# project_konovalov_motor_driver.net
KiCad netlist of a schematic drawn in Altium Designer
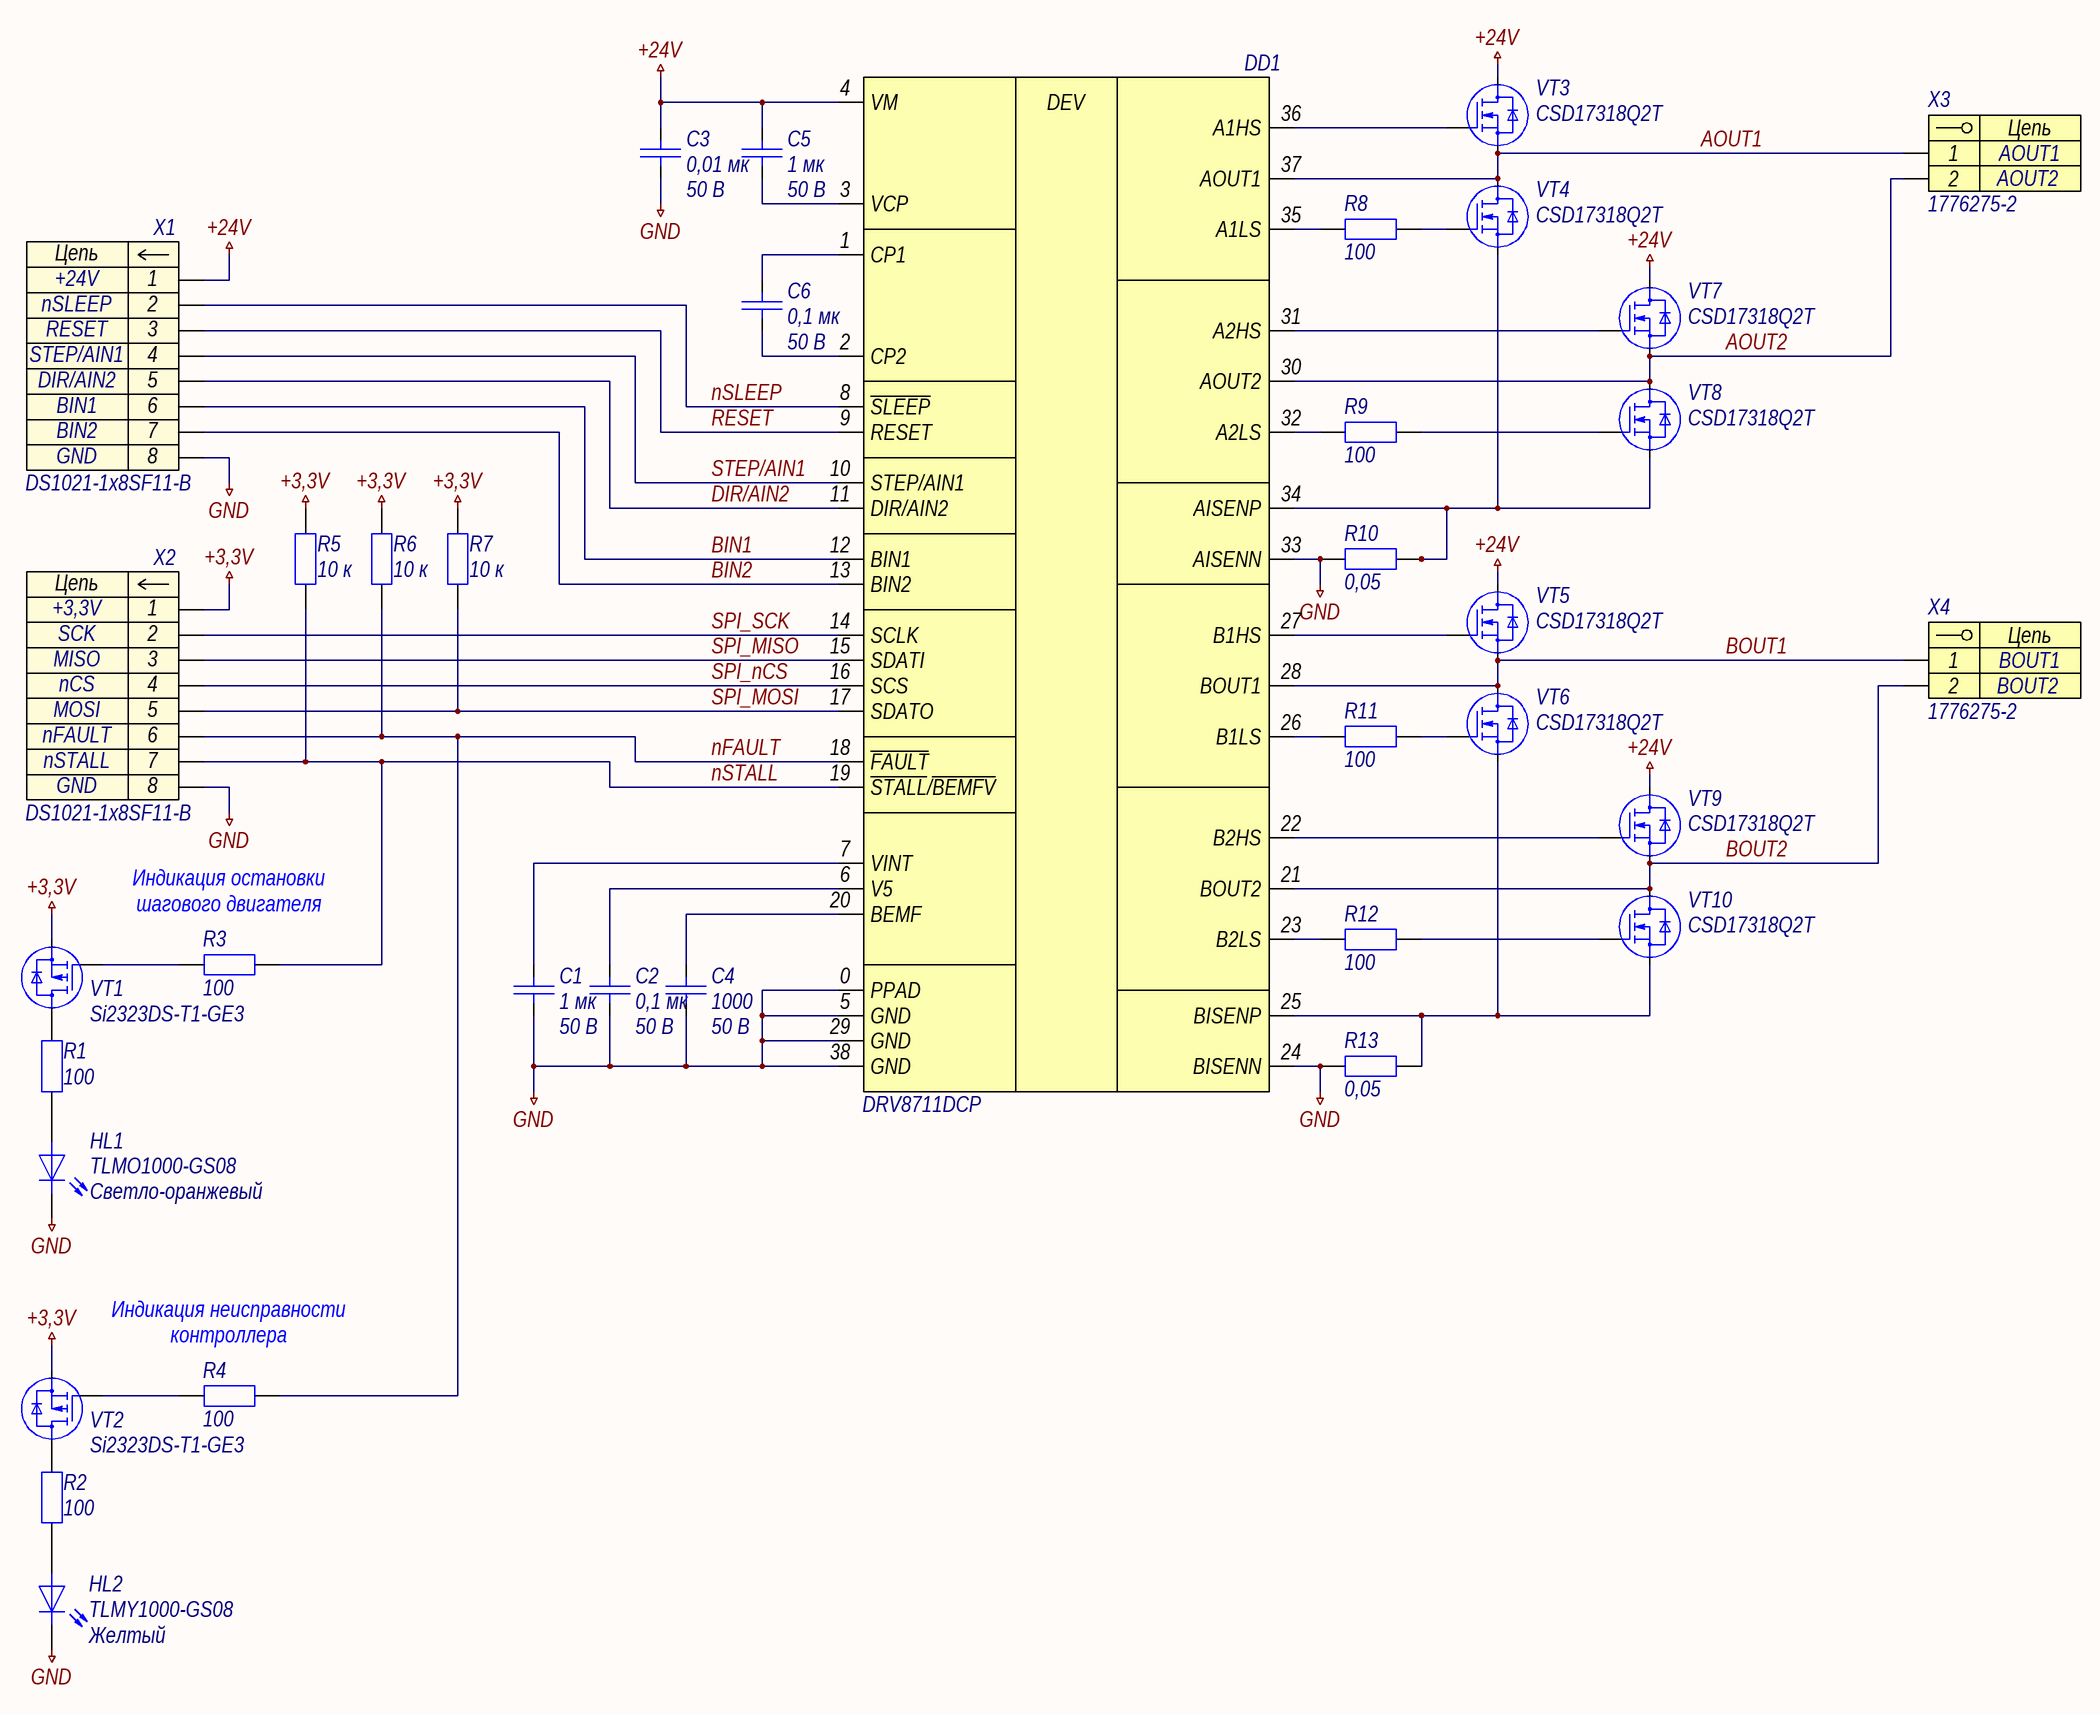
[diagram p0: project_konovalov_motor_driver.SchDoc]

(export (version "E")
  (design (tool "Eeschema 10.0.6"))
  (components
    (comp (ref "C1")
      (value "1 мк")
      (footprint "C0603")
      (description "=Описание")
      (fields (field (name "НАПРЯЖЕНИЕ") "50 В"))
      (libsource (lib "Database_Students") (part "CAPACITOR-NONPOLAR"))
    )
    (comp (ref "C2")
      (value "0,1 мк")
      (footprint "C0603")
      (description "=Описание")
      (fields (field (name "НАПРЯЖЕНИЕ") "50 В"))
      (libsource (lib "Database_Students") (part "CAPACITOR-NONPOLAR"))
    )
    (comp (ref "C3")
      (value "0,01 мк")
      (footprint "C0603")
      (description "=Описание")
      (fields (field (name "НАПРЯЖЕНИЕ") "50 В"))
      (libsource (lib "Database_Students") (part "CAPACITOR-NONPOLAR"))
    )
    (comp (ref "C4")
      (value "1000")
      (footprint "C0603")
      (description "=Описание")
      (fields (field (name "НАПРЯЖЕНИЕ") "50 В"))
      (libsource (lib "Database_Students") (part "CAPACITOR-NONPOLAR"))
    )
    (comp (ref "C5")
      (value "1 мк")
      (footprint "C0603")
      (description "=Описание")
      (fields (field (name "НАПРЯЖЕНИЕ") "50 В"))
      (libsource (lib "Database_Students") (part "CAPACITOR-NONPOLAR"))
    )
    (comp (ref "C6")
      (value "0,1 мк")
      (footprint "C0603")
      (description "=Описание")
      (fields (field (name "НАПРЯЖЕНИЕ") "50 В"))
      (libsource (lib "Database_Students") (part "CAPACITOR-NONPOLAR"))
    )
    (comp (ref "DD1")
      (value "DRV8711DCP")
      (footprint "HTSSOP-38-P50-470X290X120-L63X22-T470X290")
      (description "=Описание")
      (libsource (lib "Database_Students") (part "DRV8711DCP"))
    )
    (comp (ref "HL1")
      (value "TLMO1000-GS08")
      (footprint "HL0603")
      (description "=Описание")
      (fields (field (name "ЦВЕТ") "Светло-оранжевый"))
      (libsource (lib "Database_Students") (part "LED-COMMON"))
    )
    (comp (ref "HL2")
      (value "TLMY1000-GS08")
      (footprint "HL0603")
      (description "=Описание")
      (fields (field (name "ЦВЕТ") "Желтый"))
      (libsource (lib "Database_Students") (part "LED-COMMON"))
    )
    (comp (ref "R1")
      (value "100")
      (footprint "R0603")
      (description "=Описание")
      (libsource (lib "Database_Students") (part "RESISTOR-COMMON"))
    )
    (comp (ref "R2")
      (value "100")
      (footprint "R0603")
      (description "=Описание")
      (libsource (lib "Database_Students") (part "RESISTOR-COMMON"))
    )
    (comp (ref "R3")
      (value "100")
      (footprint "R0603")
      (description "=Описание")
      (libsource (lib "Database_Students") (part "RESISTOR-COMMON"))
    )
    (comp (ref "R4")
      (value "100")
      (footprint "R0603")
      (description "=Описание")
      (libsource (lib "Database_Students") (part "RESISTOR-COMMON"))
    )
    (comp (ref "R5")
      (value "10 к")
      (footprint "R0603")
      (description "=Описание")
      (libsource (lib "Database_Students") (part "RESISTOR-COMMON"))
    )
    (comp (ref "R6")
      (value "10 к")
      (footprint "R0603")
      (description "=Описание")
      (libsource (lib "Database_Students") (part "RESISTOR-COMMON"))
    )
    (comp (ref "R7")
      (value "10 к")
      (footprint "R0603")
      (description "=Описание")
      (libsource (lib "Database_Students") (part "RESISTOR-COMMON"))
    )
    (comp (ref "R8")
      (value "100")
      (footprint "R0603")
      (description "=Описание")
      (libsource (lib "Database_Students") (part "RESISTOR-COMMON"))
    )
    (comp (ref "R9")
      (value "100")
      (footprint "R0603")
      (description "=Описание")
      (libsource (lib "Database_Students") (part "RESISTOR-COMMON"))
    )
    (comp (ref "R10")
      (value "0,05")
      (footprint "R0603")
      (description "=Описание")
      (libsource (lib "Database_Students") (part "RESISTOR-COMMON"))
    )
    (comp (ref "R11")
      (value "100")
      (footprint "R0603")
      (description "=Описание")
      (libsource (lib "Database_Students") (part "RESISTOR-COMMON"))
    )
    (comp (ref "R12")
      (value "100")
      (footprint "R0603")
      (description "=Описание")
      (libsource (lib "Database_Students") (part "RESISTOR-COMMON"))
    )
    (comp (ref "R13")
      (value "0,05")
      (footprint "R0603")
      (description "=Описание")
      (libsource (lib "Database_Students") (part "RESISTOR-COMMON"))
    )
    (comp (ref "VT1")
      (value "Si2323DS-T1-GE3")
      (footprint "SOT-23-3-P95-292X237X112")
      (description "=Описание")
      (libsource (lib "Database_Students") (part "MOSFET-P-DIODE"))
    )
    (comp (ref "VT2")
      (value "Si2323DS-T1-GE3")
      (footprint "SOT-23-3-P95-292X237X112")
      (description "=Описание")
      (libsource (lib "Database_Students") (part "MOSFET-P-DIODE"))
    )
    (comp (ref "VT3")
      (value "CSD17318Q2T")
      (footprint "WSON-6-P65-200X200X80")
      (description "=Описание")
      (libsource (lib "Database_Students") (part "MOSFET-N-DIODE"))
    )
    (comp (ref "VT4")
      (value "CSD17318Q2T")
      (footprint "WSON-6-P65-200X200X80")
      (description "=Описание")
      (libsource (lib "Database_Students") (part "MOSFET-N-DIODE"))
    )
    (comp (ref "VT5")
      (value "CSD17318Q2T")
      (footprint "WSON-6-P65-200X200X80")
      (description "=Описание")
      (libsource (lib "Database_Students") (part "MOSFET-N-DIODE"))
    )
    (comp (ref "VT6")
      (value "CSD17318Q2T")
      (footprint "WSON-6-P65-200X200X80")
      (description "=Описание")
      (libsource (lib "Database_Students") (part "MOSFET-N-DIODE"))
    )
    (comp (ref "VT7")
      (value "CSD17318Q2T")
      (footprint "WSON-6-P65-200X200X80")
      (description "=Описание")
      (libsource (lib "Database_Students") (part "MOSFET-N-DIODE"))
    )
    (comp (ref "VT8")
      (value "CSD17318Q2T")
      (footprint "WSON-6-P65-200X200X80")
      (description "=Описание")
      (libsource (lib "Database_Students") (part "MOSFET-N-DIODE"))
    )
    (comp (ref "VT9")
      (value "CSD17318Q2T")
      (footprint "WSON-6-P65-200X200X80")
      (description "=Описание")
      (libsource (lib "Database_Students") (part "MOSFET-N-DIODE"))
    )
    (comp (ref "VT10")
      (value "CSD17318Q2T")
      (footprint "WSON-6-P65-200X200X80")
      (description "=Описание")
      (libsource (lib "Database_Students") (part "MOSFET-N-DIODE"))
    )
    (comp (ref "X1")
      (value "DS1021-1x8SF11-B")
      (footprint "DS1021-1X8SF11-B")
      (description "=Описание")
      (libsource (lib "Database_Students") (part "HEADER-8-PLG"))
    )
    (comp (ref "X2")
      (value "DS1021-1x8SF11-B")
      (footprint "DS1021-1X8SF11-B")
      (description "=Описание")
      (libsource (lib "Database_Students") (part "HEADER-8-PLG"))
    )
    (comp (ref "X3")
      (value "1776275-2")
      (footprint "1776275-2")
      (description "=Описание")
      (libsource (lib "Database_Students") (part "HEADER-2-TRM"))
    )
    (comp (ref "X4")
      (value "1776275-2")
      (footprint "1776275-2")
      (description "=Описание")
      (libsource (lib "Database_Students") (part "HEADER-2-TRM"))
    )
  )
  (nets
    (net (code "1") (name "+3,3V") (class "Default")
      (node (ref "R5") (pin "2") (pinfunction "2_2") (pintype "passive"))
      (node (ref "R6") (pin "2") (pinfunction "2_2") (pintype "passive"))
      (node (ref "R7") (pin "2") (pinfunction "2_2") (pintype "passive"))
      (node (ref "VT1") (pin "S") (pinfunction "S_S") (pintype "passive"))
      (node (ref "VT2") (pin "S") (pinfunction "S_S") (pintype "passive"))
      (node (ref "X2") (pin "1") (pinfunction "1_1") (pintype "passive"))
    )
    (net (code "2") (name "+24V") (class "Default")
      (node (ref "C3") (pin "1") (pinfunction "1_1") (pintype "passive"))
      (node (ref "C5") (pin "1") (pinfunction "1_1") (pintype "passive"))
      (node (ref "DD1") (pin "4") (pinfunction "VM_4") (pintype "passive"))
      (node (ref "VT3") (pin "D") (pinfunction "D_D") (pintype "passive"))
      (node (ref "VT5") (pin "D") (pinfunction "D_D") (pintype "passive"))
      (node (ref "VT7") (pin "D") (pinfunction "D_D") (pintype "passive"))
      (node (ref "VT9") (pin "D") (pinfunction "D_D") (pintype "passive"))
      (node (ref "X1") (pin "1") (pinfunction "1_1") (pintype "passive"))
    )
    (net (code "3") (name "/AOUT1") (class "Default")
      (node (ref "DD1") (pin "37") (pinfunction "AOUT1_37") (pintype "passive"))
      (node (ref "VT3") (pin "S") (pinfunction "S_S") (pintype "passive"))
      (node (ref "VT4") (pin "D") (pinfunction "D_D") (pintype "passive"))
      (node (ref "X3") (pin "1") (pinfunction "1_1") (pintype "passive"))
    )
    (net (code "4") (name "/AOUT2") (class "Default")
      (node (ref "DD1") (pin "30") (pinfunction "AOUT2_30") (pintype "passive"))
      (node (ref "VT7") (pin "S") (pinfunction "S_S") (pintype "passive"))
      (node (ref "VT8") (pin "D") (pinfunction "D_D") (pintype "passive"))
      (node (ref "X3") (pin "2") (pinfunction "2_2") (pintype "passive"))
    )
    (net (code "5") (name "/BIN1") (class "Default")
      (node (ref "DD1") (pin "12") (pinfunction "BIN1_12") (pintype "passive"))
      (node (ref "X1") (pin "6") (pinfunction "6_6") (pintype "passive"))
    )
    (net (code "6") (name "/BIN2") (class "Default")
      (node (ref "DD1") (pin "13") (pinfunction "BIN2_13") (pintype "passive"))
      (node (ref "X1") (pin "7") (pinfunction "7_7") (pintype "passive"))
    )
    (net (code "7") (name "/BOUT1") (class "Default")
      (node (ref "DD1") (pin "28") (pinfunction "BOUT1_28") (pintype "passive"))
      (node (ref "VT5") (pin "S") (pinfunction "S_S") (pintype "passive"))
      (node (ref "VT6") (pin "D") (pinfunction "D_D") (pintype "passive"))
      (node (ref "X4") (pin "1") (pinfunction "1_1") (pintype "passive"))
    )
    (net (code "8") (name "/BOUT2") (class "Default")
      (node (ref "DD1") (pin "21") (pinfunction "BOUT2_21") (pintype "passive"))
      (node (ref "VT10") (pin "D") (pinfunction "D_D") (pintype "passive"))
      (node (ref "VT9") (pin "S") (pinfunction "S_S") (pintype "passive"))
      (node (ref "X4") (pin "2") (pinfunction "2_2") (pintype "passive"))
    )
    (net (code "9") (name "/DIR{slash}AIN2") (class "Default")
      (node (ref "DD1") (pin "11") (pinfunction "DIR/AIN2_11") (pintype "passive"))
      (node (ref "X1") (pin "5") (pinfunction "5_5") (pintype "passive"))
    )
    (net (code "10") (name "/RESET") (class "Default")
      (node (ref "DD1") (pin "9") (pinfunction "RESET_9") (pintype "passive"))
      (node (ref "X1") (pin "3") (pinfunction "3_3") (pintype "passive"))
    )
    (net (code "11") (name "/SPI_MISO") (class "Default")
      (node (ref "DD1") (pin "15") (pinfunction "SDATI_15") (pintype "passive"))
      (node (ref "X2") (pin "3") (pinfunction "3_3") (pintype "passive"))
    )
    (net (code "12") (name "/SPI_MOSI") (class "Default")
      (node (ref "DD1") (pin "17") (pinfunction "SDATO_17") (pintype "passive"))
      (node (ref "R7") (pin "1") (pinfunction "1_1") (pintype "passive"))
      (node (ref "X2") (pin "5") (pinfunction "5_5") (pintype "passive"))
    )
    (net (code "13") (name "/SPI_SCK") (class "Default")
      (node (ref "DD1") (pin "14") (pinfunction "SCLK_14") (pintype "passive"))
      (node (ref "X2") (pin "2") (pinfunction "2_2") (pintype "passive"))
    )
    (net (code "14") (name "/SPI_nCS") (class "Default")
      (node (ref "DD1") (pin "16") (pinfunction "SCS_16") (pintype "passive"))
      (node (ref "X2") (pin "4") (pinfunction "4_4") (pintype "passive"))
    )
    (net (code "15") (name "/STEP{slash}AIN1") (class "Default")
      (node (ref "DD1") (pin "10") (pinfunction "STEP/AIN1_10") (pintype "passive"))
      (node (ref "X1") (pin "4") (pinfunction "4_4") (pintype "passive"))
    )
    (net (code "16") (name "/nFAULT") (class "Default")
      (node (ref "DD1") (pin "18") (pinfunction "~{FAULT}_18") (pintype "passive"))
      (node (ref "R4") (pin "2") (pinfunction "2_2") (pintype "passive"))
      (node (ref "R6") (pin "1") (pinfunction "1_1") (pintype "passive"))
      (node (ref "X2") (pin "6") (pinfunction "6_6") (pintype "passive"))
    )
    (net (code "17") (name "/nSLEEP") (class "Default")
      (node (ref "DD1") (pin "8") (pinfunction "~{SLEEP}_8") (pintype "passive"))
      (node (ref "X1") (pin "2") (pinfunction "2_2") (pintype "passive"))
    )
    (net (code "18") (name "/nSTALL") (class "Default")
      (node (ref "DD1") (pin "19") (pinfunction "~{STALL}/~{BEMFV}_19") (pintype "passive"))
      (node (ref "R3") (pin "2") (pinfunction "2_2") (pintype "passive"))
      (node (ref "R5") (pin "1") (pinfunction "1_1") (pintype "passive"))
      (node (ref "X2") (pin "7") (pinfunction "7_7") (pintype "passive"))
    )
    (net (code "19") (name "GND") (class "Default")
      (node (ref "C1") (pin "2") (pinfunction "2_2") (pintype "passive"))
      (node (ref "C2") (pin "2") (pinfunction "2_2") (pintype "passive"))
      (node (ref "C3") (pin "2") (pinfunction "2_2") (pintype "passive"))
      (node (ref "C4") (pin "2") (pinfunction "2_2") (pintype "passive"))
      (node (ref "DD1") (pin "0") (pinfunction "PPAD_0") (pintype "passive"))
      (node (ref "DD1") (pin "24") (pinfunction "BISENN_24") (pintype "passive"))
      (node (ref "DD1") (pin "29") (pinfunction "GND_29") (pintype "passive"))
      (node (ref "DD1") (pin "33") (pinfunction "AISENN_33") (pintype "passive"))
      (node (ref "DD1") (pin "38") (pinfunction "GND_38") (pintype "passive"))
      (node (ref "DD1") (pin "5") (pinfunction "GND_5") (pintype "passive"))
      (node (ref "HL1") (pin "1") (pinfunction "1_1") (pintype "passive"))
      (node (ref "HL2") (pin "1") (pinfunction "1_1") (pintype "passive"))
      (node (ref "R10") (pin "1") (pinfunction "1_1") (pintype "passive"))
      (node (ref "R13") (pin "1") (pinfunction "1_1") (pintype "passive"))
      (node (ref "X1") (pin "8") (pinfunction "8_8") (pintype "passive"))
      (node (ref "X2") (pin "8") (pinfunction "8_8") (pintype "passive"))
    )
    (net (code "20") (name "Net-(DD1-A1HS)") (class "Default")
      (node (ref "DD1") (pin "36") (pinfunction "A1HS_36") (pintype "passive"))
      (node (ref "VT3") (pin "G") (pinfunction "G_G") (pintype "passive"))
    )
    (net (code "21") (name "Net-(DD1-A1LS)") (class "Default")
      (node (ref "DD1") (pin "35") (pinfunction "A1LS_35") (pintype "passive"))
      (node (ref "R8") (pin "1") (pinfunction "1_1") (pintype "passive"))
    )
    (net (code "22") (name "Net-(DD1-A2HS)") (class "Default")
      (node (ref "DD1") (pin "31") (pinfunction "A2HS_31") (pintype "passive"))
      (node (ref "VT7") (pin "G") (pinfunction "G_G") (pintype "passive"))
    )
    (net (code "23") (name "Net-(DD1-A2LS)") (class "Default")
      (node (ref "DD1") (pin "32") (pinfunction "A2LS_32") (pintype "passive"))
      (node (ref "R9") (pin "1") (pinfunction "1_1") (pintype "passive"))
    )
    (net (code "24") (name "Net-(DD1-AISENP)") (class "Default")
      (node (ref "DD1") (pin "34") (pinfunction "AISENP_34") (pintype "passive"))
      (node (ref "R10") (pin "2") (pinfunction "2_2") (pintype "passive"))
      (node (ref "VT4") (pin "S") (pinfunction "S_S") (pintype "passive"))
      (node (ref "VT8") (pin "S") (pinfunction "S_S") (pintype "passive"))
    )
    (net (code "25") (name "Net-(DD1-B1HS)") (class "Default")
      (node (ref "DD1") (pin "27") (pinfunction "B1HS_27") (pintype "passive"))
      (node (ref "VT5") (pin "G") (pinfunction "G_G") (pintype "passive"))
    )
    (net (code "26") (name "Net-(DD1-B1LS)") (class "Default")
      (node (ref "DD1") (pin "26") (pinfunction "B1LS_26") (pintype "passive"))
      (node (ref "R11") (pin "1") (pinfunction "1_1") (pintype "passive"))
    )
    (net (code "27") (name "Net-(DD1-B2HS)") (class "Default")
      (node (ref "DD1") (pin "22") (pinfunction "B2HS_22") (pintype "passive"))
      (node (ref "VT9") (pin "G") (pinfunction "G_G") (pintype "passive"))
    )
    (net (code "28") (name "Net-(DD1-B2LS)") (class "Default")
      (node (ref "DD1") (pin "23") (pinfunction "B2LS_23") (pintype "passive"))
      (node (ref "R12") (pin "1") (pinfunction "1_1") (pintype "passive"))
    )
    (net (code "29") (name "Net-(DD1-BEMF)") (class "Default")
      (node (ref "C4") (pin "1") (pinfunction "1_1") (pintype "passive"))
      (node (ref "DD1") (pin "20") (pinfunction "BEMF_20") (pintype "passive"))
    )
    (net (code "30") (name "Net-(DD1-BISENP)") (class "Default")
      (node (ref "DD1") (pin "25") (pinfunction "BISENP_25") (pintype "passive"))
      (node (ref "R13") (pin "2") (pinfunction "2_2") (pintype "passive"))
      (node (ref "VT10") (pin "S") (pinfunction "S_S") (pintype "passive"))
      (node (ref "VT6") (pin "S") (pinfunction "S_S") (pintype "passive"))
    )
    (net (code "31") (name "Net-(DD1-CP1)") (class "Default")
      (node (ref "C6") (pin "1") (pinfunction "1_1") (pintype "passive"))
      (node (ref "DD1") (pin "1") (pinfunction "CP1_1") (pintype "passive"))
    )
    (net (code "32") (name "Net-(DD1-CP2)") (class "Default")
      (node (ref "C6") (pin "2") (pinfunction "2_2") (pintype "passive"))
      (node (ref "DD1") (pin "2") (pinfunction "CP2_2") (pintype "passive"))
    )
    (net (code "33") (name "Net-(DD1-V5)") (class "Default")
      (node (ref "C2") (pin "1") (pinfunction "1_1") (pintype "passive"))
      (node (ref "DD1") (pin "6") (pinfunction "V5_6") (pintype "passive"))
    )
    (net (code "34") (name "Net-(DD1-VCP)") (class "Default")
      (node (ref "C5") (pin "2") (pinfunction "2_2") (pintype "passive"))
      (node (ref "DD1") (pin "3") (pinfunction "VCP_3") (pintype "passive"))
    )
    (net (code "35") (name "Net-(DD1-VINT)") (class "Default")
      (node (ref "C1") (pin "1") (pinfunction "1_1") (pintype "passive"))
      (node (ref "DD1") (pin "7") (pinfunction "VINT_7") (pintype "passive"))
    )
    (net (code "36") (name "Net-(HL1-Pad2)") (class "Default")
      (node (ref "HL1") (pin "2") (pinfunction "2_2") (pintype "passive"))
      (node (ref "R1") (pin "1") (pinfunction "1_1") (pintype "passive"))
    )
    (net (code "37") (name "Net-(HL2-Pad2)") (class "Default")
      (node (ref "HL2") (pin "2") (pinfunction "2_2") (pintype "passive"))
      (node (ref "R2") (pin "1") (pinfunction "1_1") (pintype "passive"))
    )
    (net (code "38") (name "Net-(R1-Pad2)") (class "Default")
      (node (ref "R1") (pin "2") (pinfunction "2_2") (pintype "passive"))
      (node (ref "VT1") (pin "D") (pinfunction "D_D") (pintype "passive"))
    )
    (net (code "39") (name "Net-(R2-Pad2)") (class "Default")
      (node (ref "R2") (pin "2") (pinfunction "2_2") (pintype "passive"))
      (node (ref "VT2") (pin "D") (pinfunction "D_D") (pintype "passive"))
    )
    (net (code "40") (name "Net-(R3-Pad1)") (class "Default")
      (node (ref "R3") (pin "1") (pinfunction "1_1") (pintype "passive"))
      (node (ref "VT1") (pin "G") (pinfunction "G_G") (pintype "passive"))
    )
    (net (code "41") (name "Net-(R4-Pad1)") (class "Default")
      (node (ref "R4") (pin "1") (pinfunction "1_1") (pintype "passive"))
      (node (ref "VT2") (pin "G") (pinfunction "G_G") (pintype "passive"))
    )
    (net (code "42") (name "Net-(R8-Pad2)") (class "Default")
      (node (ref "R8") (pin "2") (pinfunction "2_2") (pintype "passive"))
      (node (ref "VT4") (pin "G") (pinfunction "G_G") (pintype "passive"))
    )
    (net (code "43") (name "Net-(R9-Pad2)") (class "Default")
      (node (ref "R9") (pin "2") (pinfunction "2_2") (pintype "passive"))
      (node (ref "VT8") (pin "G") (pinfunction "G_G") (pintype "passive"))
    )
    (net (code "44") (name "Net-(R11-Pad2)") (class "Default")
      (node (ref "R11") (pin "2") (pinfunction "2_2") (pintype "passive"))
      (node (ref "VT6") (pin "G") (pinfunction "G_G") (pintype "passive"))
    )
    (net (code "45") (name "Net-(R12-Pad2)") (class "Default")
      (node (ref "R12") (pin "2") (pinfunction "2_2") (pintype "passive"))
      (node (ref "VT10") (pin "G") (pinfunction "G_G") (pintype "passive"))
    )
  )
)
